# NanoV3_3_new_board.net
KiCad netlist of a schematic drawn in EAGLE
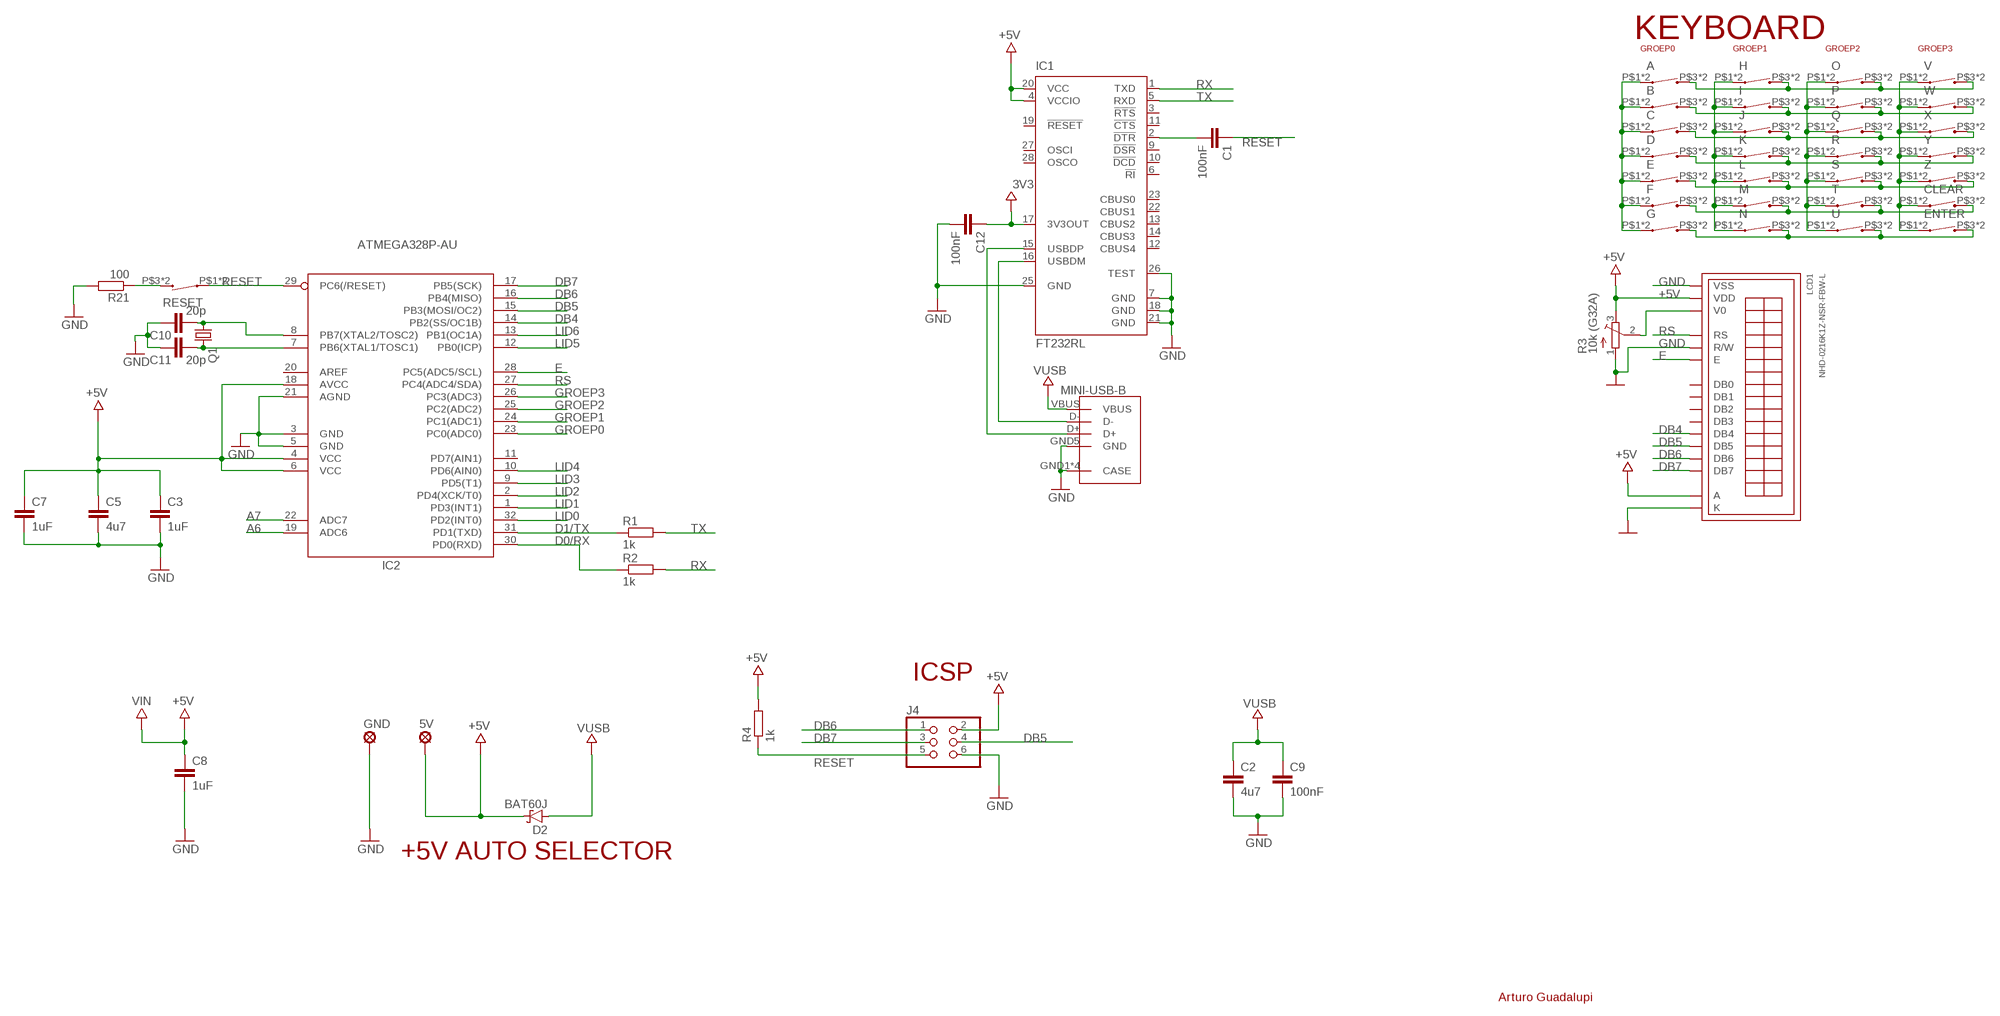
[diagram p0: schematic, sheet 1]

(export (version "E")
  (design (tool "Eeschema 10.0.6"))
  (components
    (comp (ref "5V")
      (value "LSP10")
      (footprint "eagle-import:LSP10")
      (libsource (lib "eagle-import") (part "LSP10"))
    )
    (comp (ref "A")
      (value "BRIGHTTSA061G100-250_SWITCH")
      (footprint "eagle-import:BRIGHTTSA061G100-250")
      (libsource (lib "eagle-import") (part "BRIGHTTSA061G100-250_SWITCH"))
    )
    (comp (ref "B")
      (value "BRIGHTTSA061G100-250_SWITCH")
      (footprint "eagle-import:BRIGHTTSA061G100-250")
      (libsource (lib "eagle-import") (part "BRIGHTTSA061G100-250_SWITCH"))
    )
    (comp (ref "C")
      (value "BRIGHTTSA061G100-250_SWITCH")
      (footprint "eagle-import:BRIGHTTSA061G100-250")
      (libsource (lib "eagle-import") (part "BRIGHTTSA061G100-250_SWITCH"))
    )
    (comp (ref "C1")
      (value "100nF")
      (footprint "eagle-import:C0805")
      (libsource (lib "eagle-import") (part "C-EUC0805"))
    )
    (comp (ref "C2")
      (value "4u7")
      (footprint "eagle-import:C0805")
      (libsource (lib "eagle-import") (part "C-EUC0805"))
    )
    (comp (ref "C3")
      (value "1uF")
      (footprint "eagle-import:C0805")
      (libsource (lib "eagle-import") (part "C-EUC0805"))
    )
    (comp (ref "C5")
      (value "4u7")
      (footprint "eagle-import:C0805")
      (libsource (lib "eagle-import") (part "C-EUC0805"))
    )
    (comp (ref "C7")
      (value "1uF")
      (footprint "eagle-import:C0805")
      (libsource (lib "eagle-import") (part "C-EUC0805"))
    )
    (comp (ref "C8")
      (value "1uF")
      (footprint "eagle-import:C0805")
      (libsource (lib "eagle-import") (part "C-EUC0805"))
    )
    (comp (ref "C9")
      (value "100nF")
      (footprint "eagle-import:C0805")
      (libsource (lib "eagle-import") (part "C-EUC0805"))
    )
    (comp (ref "C10")
      (value "20p")
      (footprint "eagle-import:C0805")
      (libsource (lib "eagle-import") (part "C-EUC0805"))
    )
    (comp (ref "C11")
      (value "20p")
      (footprint "eagle-import:C0805")
      (libsource (lib "eagle-import") (part "C-EUC0805"))
    )
    (comp (ref "C12")
      (value "100nF")
      (footprint "eagle-import:C0805")
      (libsource (lib "eagle-import") (part "C-EUC0805"))
    )
    (comp (ref "CLEAR")
      (value "BRIGHTTSA061G100-250_SWITCH")
      (footprint "eagle-import:BRIGHTTSA061G100-250")
      (libsource (lib "eagle-import") (part "BRIGHTTSA061G100-250_SWITCH"))
    )
    (comp (ref "D")
      (value "BRIGHTTSA061G100-250_SWITCH")
      (footprint "eagle-import:BRIGHTTSA061G100-250")
      (libsource (lib "eagle-import") (part "BRIGHTTSA061G100-250_SWITCH"))
    )
    (comp (ref "D2")
      (value "BAT60J")
      (footprint "eagle-import:SOD323_ST")
      (libsource (lib "eagle-import") (part "BAT60J"))
    )
    (comp (ref "E")
      (value "BRIGHTTSA061G100-250_SWITCH")
      (footprint "eagle-import:BRIGHTTSA061G100-250")
      (libsource (lib "eagle-import") (part "BRIGHTTSA061G100-250_SWITCH"))
    )
    (comp (ref "ENTER")
      (value "BRIGHTTSA061G100-250_SWITCH")
      (footprint "eagle-import:BRIGHTTSA061G100-250")
      (libsource (lib "eagle-import") (part "BRIGHTTSA061G100-250_SWITCH"))
    )
    (comp (ref "F")
      (value "BRIGHTTSA061G100-250_SWITCH")
      (footprint "eagle-import:BRIGHTTSA061G100-250")
      (libsource (lib "eagle-import") (part "BRIGHTTSA061G100-250_SWITCH"))
    )
    (comp (ref "G")
      (value "BRIGHTTSA061G100-250_SWITCH")
      (footprint "eagle-import:BRIGHTTSA061G100-250")
      (libsource (lib "eagle-import") (part "BRIGHTTSA061G100-250_SWITCH"))
    )
    (comp (ref "GND")
      (value "LSP10")
      (footprint "eagle-import:LSP10")
      (libsource (lib "eagle-import") (part "LSP10"))
    )
    (comp (ref "H")
      (value "BRIGHTTSA061G100-250_SWITCH")
      (footprint "eagle-import:BRIGHTTSA061G100-250")
      (libsource (lib "eagle-import") (part "BRIGHTTSA061G100-250_SWITCH"))
    )
    (comp (ref "I")
      (value "BRIGHTTSA061G100-250_SWITCH")
      (footprint "eagle-import:BRIGHTTSA061G100-250")
      (libsource (lib "eagle-import") (part "BRIGHTTSA061G100-250_SWITCH"))
    )
    (comp (ref "IC1")
      (value "FT232RL")
      (footprint "eagle-import:SSOP28")
      (libsource (lib "eagle-import") (part "FT232RL"))
    )
    (comp (ref "IC2")
      (value "ATMEGA328P-AU")
      (footprint "eagle-import:TQFP32-08")
      (fields (field (name "MANUFACTURER") "ATMEL"))
      (libsource (lib "eagle-import") (part "ATMEGA328P-32AU"))
    )
    (comp (ref "J")
      (value "BRIGHTTSA061G100-250_SWITCH")
      (footprint "eagle-import:BRIGHTTSA061G100-250")
      (libsource (lib "eagle-import") (part "BRIGHTTSA061G100-250_SWITCH"))
    )
    (comp (ref "J4")
      (value "0114_PH254-203DF118A00V")
      (footprint "eagle-import:2X03")
      (fields (field (name "PART_NUMBER") "PH254-203DF118A00V"))
      (libsource (lib "eagle-import") (part "0114_PH254-203DF118A00V"))
    )
    (comp (ref "K")
      (value "BRIGHTTSA061G100-250_SWITCH")
      (footprint "eagle-import:BRIGHTTSA061G100-250")
      (libsource (lib "eagle-import") (part "BRIGHTTSA061G100-250_SWITCH"))
    )
    (comp (ref "L")
      (value "BRIGHTTSA061G100-250_SWITCH")
      (footprint "eagle-import:BRIGHTTSA061G100-250")
      (libsource (lib "eagle-import") (part "BRIGHTTSA061G100-250_SWITCH"))
    )
    (comp (ref "LCD1")
      (value "NHD-0216K1Z-NSR-FBW-L")
      (footprint "eagle-import:LCD_NO-HEAD")
      (libsource (lib "eagle-import") (part "GEN-DISPLAY-16X2-LCD"))
    )
    (comp (ref "M")
      (value "BRIGHTTSA061G100-250_SWITCH")
      (footprint "eagle-import:BRIGHTTSA061G100-250")
      (libsource (lib "eagle-import") (part "BRIGHTTSA061G100-250_SWITCH"))
    )
    (comp (ref "MINI-USB-B")
      (value "MINI_USB_B-KRHRO-SELECU-M-M5DS-W-4")
      (footprint "eagle-import:KRHROSELECU-M-M5DS-W-4")
      (libsource (lib "eagle-import") (part "MINI_USB_B-KRHRO-SELECU-M-M5DS-W-4"))
    )
    (comp (ref "N")
      (value "BRIGHTTSA061G100-250_SWITCH")
      (footprint "eagle-import:BRIGHTTSA061G100-250")
      (libsource (lib "eagle-import") (part "BRIGHTTSA061G100-250_SWITCH"))
    )
    (comp (ref "O")
      (value "BRIGHTTSA061G100-250_SWITCH")
      (footprint "eagle-import:BRIGHTTSA061G100-250")
      (libsource (lib "eagle-import") (part "BRIGHTTSA061G100-250_SWITCH"))
    )
    (comp (ref "P")
      (value "BRIGHTTSA061G100-250_SWITCH")
      (footprint "eagle-import:BRIGHTTSA061G100-250")
      (libsource (lib "eagle-import") (part "BRIGHTTSA061G100-250_SWITCH"))
    )
    (comp (ref "Q")
      (value "BRIGHTTSA061G100-250_SWITCH")
      (footprint "eagle-import:BRIGHTTSA061G100-250")
      (libsource (lib "eagle-import") (part "BRIGHTTSA061G100-250_SWITCH"))
    )
    (comp (ref "Q1")
      (value "CRYSTALHC49U70")
      (footprint "eagle-import:HC49U70")
      (libsource (lib "eagle-import") (part "CRYSTALHC49U70"))
    )
    (comp (ref "R")
      (value "BRIGHTTSA061G100-250_SWITCH")
      (footprint "eagle-import:BRIGHTTSA061G100-250")
      (libsource (lib "eagle-import") (part "BRIGHTTSA061G100-250_SWITCH"))
    )
    (comp (ref "R1")
      (value "1k")
      (footprint "eagle-import:R0805")
      (libsource (lib "eagle-import") (part "R-EU_R0805"))
    )
    (comp (ref "R2")
      (value "1k")
      (footprint "eagle-import:R0805")
      (libsource (lib "eagle-import") (part "R-EU_R0805"))
    )
    (comp (ref "R3")
      (value "10k (G32A)")
      (footprint "eagle-import:3223W")
      (libsource (lib "eagle-import") (part "TRIM_EU-3223W"))
    )
    (comp (ref "R4")
      (value "1k")
      (footprint "eagle-import:R0805")
      (libsource (lib "eagle-import") (part "R-EU_R0805"))
    )
    (comp (ref "R21")
      (value "100")
      (footprint "eagle-import:R0805")
      (libsource (lib "eagle-import") (part "R-EU_R0805"))
    )
    (comp (ref "RESET")
      (value "BRIGHTTSA061G100-250_SWITCH")
      (footprint "eagle-import:BRIGHTTSA061G100-250")
      (libsource (lib "eagle-import") (part "BRIGHTTSA061G100-250_SWITCH"))
    )
    (comp (ref "S")
      (value "BRIGHTTSA061G100-250_SWITCH")
      (footprint "eagle-import:BRIGHTTSA061G100-250")
      (libsource (lib "eagle-import") (part "BRIGHTTSA061G100-250_SWITCH"))
    )
    (comp (ref "T")
      (value "BRIGHTTSA061G100-250_SWITCH")
      (footprint "eagle-import:BRIGHTTSA061G100-250")
      (libsource (lib "eagle-import") (part "BRIGHTTSA061G100-250_SWITCH"))
    )
    (comp (ref "U")
      (value "BRIGHTTSA061G100-250_SWITCH")
      (footprint "eagle-import:BRIGHTTSA061G100-250")
      (libsource (lib "eagle-import") (part "BRIGHTTSA061G100-250_SWITCH"))
    )
    (comp (ref "V")
      (value "BRIGHTTSA061G100-250_SWITCH")
      (footprint "eagle-import:BRIGHTTSA061G100-250")
      (libsource (lib "eagle-import") (part "BRIGHTTSA061G100-250_SWITCH"))
    )
    (comp (ref "W")
      (value "BRIGHTTSA061G100-250_SWITCH")
      (footprint "eagle-import:BRIGHTTSA061G100-250")
      (libsource (lib "eagle-import") (part "BRIGHTTSA061G100-250_SWITCH"))
    )
    (comp (ref "X")
      (value "BRIGHTTSA061G100-250_SWITCH")
      (footprint "eagle-import:BRIGHTTSA061G100-250")
      (libsource (lib "eagle-import") (part "BRIGHTTSA061G100-250_SWITCH"))
    )
    (comp (ref "Y")
      (value "BRIGHTTSA061G100-250_SWITCH")
      (footprint "eagle-import:BRIGHTTSA061G100-250")
      (libsource (lib "eagle-import") (part "BRIGHTTSA061G100-250_SWITCH"))
    )
    (comp (ref "Z")
      (value "BRIGHTTSA061G100-250_SWITCH")
      (footprint "eagle-import:BRIGHTTSA061G100-250")
      (libsource (lib "eagle-import") (part "BRIGHTTSA061G100-250_SWITCH"))
    )
  )
  (nets
    (net (code "1") (name "+5V") (class "Default")
      (node (ref "5V") (pin "MP") (pinfunction "MP_MP") (pintype "passive"))
      (node (ref "C3") (pin "1") (pinfunction "1_1") (pintype "passive"))
      (node (ref "C5") (pin "1") (pinfunction "1_1") (pintype "passive"))
      (node (ref "C7") (pin "1") (pinfunction "1_1") (pintype "passive"))
      (node (ref "C8") (pin "1") (pinfunction "1_1") (pintype "passive"))
      (node (ref "D2") (pin "C") (pinfunction "C_C") (pintype "passive"))
      (node (ref "IC1") (pin "20") (pinfunction "VCC_20") (pintype "power_in"))
      (node (ref "IC1") (pin "4") (pinfunction "VCCIO_4") (pintype "power_in"))
      (node (ref "IC2") (pin "18") (pinfunction "AVCC_18") (pintype "bidirectional"))
      (node (ref "IC2") (pin "4") (pinfunction "VCC_4") (pintype "bidirectional"))
      (node (ref "IC2") (pin "6") (pinfunction "VCC_6") (pintype "bidirectional"))
      (node (ref "J4") (pin "2") (pinfunction "2_2") (pintype "passive"))
      (node (ref "LCD1") (pin "15") (pinfunction "A_15") (pintype "bidirectional"))
      (node (ref "LCD1") (pin "2") (pinfunction "VDD_2") (pintype "bidirectional"))
      (node (ref "R3") (pin "3") (pinfunction "E_3") (pintype "passive"))
      (node (ref "R4") (pin "2") (pinfunction "2_2") (pintype "passive"))
    )
    (net (code "2") (name "/A6") (class "Default")
      (node (ref "IC2") (pin "19") (pinfunction "ADC6_19") (pintype "bidirectional"))
    )
    (net (code "3") (name "/A7") (class "Default")
      (node (ref "IC2") (pin "22") (pinfunction "ADC7_22") (pintype "bidirectional"))
    )
    (net (code "4") (name "/D0{slash}RX") (class "Default")
      (node (ref "IC2") (pin "30") (pinfunction "PD0(RXD)_30") (pintype "bidirectional"))
      (node (ref "R2") (pin "1") (pinfunction "1_1") (pintype "passive"))
    )
    (net (code "5") (name "/D1{slash}TX") (class "Default")
      (node (ref "IC2") (pin "31") (pinfunction "PD1(TXD)_31") (pintype "bidirectional"))
      (node (ref "R1") (pin "1") (pinfunction "1_1") (pintype "passive"))
    )
    (net (code "6") (name "/DB4") (class "Default")
      (node (ref "IC2") (pin "14") (pinfunction "PB2(SS/OC1B)_14") (pintype "bidirectional"))
      (node (ref "LCD1") (pin "11") (pinfunction "DB4_11") (pintype "bidirectional"))
    )
    (net (code "7") (name "/DB5") (class "Default")
      (node (ref "IC2") (pin "15") (pinfunction "PB3(MOSI/OC2)_15") (pintype "bidirectional"))
      (node (ref "J4") (pin "4") (pinfunction "4_4") (pintype "passive"))
      (node (ref "LCD1") (pin "12") (pinfunction "DB5_12") (pintype "bidirectional"))
    )
    (net (code "8") (name "/DB6") (class "Default")
      (node (ref "IC2") (pin "16") (pinfunction "PB4(MISO)_16") (pintype "bidirectional"))
      (node (ref "J4") (pin "1") (pinfunction "1_1") (pintype "passive"))
      (node (ref "LCD1") (pin "13") (pinfunction "DB6_13") (pintype "bidirectional"))
    )
    (net (code "9") (name "/DB7") (class "Default")
      (node (ref "IC2") (pin "17") (pinfunction "PB5(SCK)_17") (pintype "bidirectional"))
      (node (ref "J4") (pin "3") (pinfunction "3_3") (pintype "passive"))
      (node (ref "LCD1") (pin "14") (pinfunction "DB7_14") (pintype "bidirectional"))
    )
    (net (code "10") (name "/E") (class "Default")
      (node (ref "IC2") (pin "28") (pinfunction "PC5(ADC5/SCL)_28") (pintype "bidirectional"))
      (node (ref "LCD1") (pin "6") (pinfunction "E_6") (pintype "bidirectional"))
    )
    (net (code "11") (name "/GROEP0") (class "Default")
      (node (ref "A") (pin "P$1") (pinfunction "1_P$1") (pintype "passive"))
      (node (ref "A") (pin "P$2") (pinfunction "1_P$2") (pintype "passive"))
      (node (ref "B") (pin "P$1") (pinfunction "1_P$1") (pintype "passive"))
      (node (ref "B") (pin "P$2") (pinfunction "1_P$2") (pintype "passive"))
      (node (ref "C") (pin "P$1") (pinfunction "1_P$1") (pintype "passive"))
      (node (ref "C") (pin "P$2") (pinfunction "1_P$2") (pintype "passive"))
      (node (ref "D") (pin "P$1") (pinfunction "1_P$1") (pintype "passive"))
      (node (ref "D") (pin "P$2") (pinfunction "1_P$2") (pintype "passive"))
      (node (ref "E") (pin "P$1") (pinfunction "1_P$1") (pintype "passive"))
      (node (ref "E") (pin "P$2") (pinfunction "1_P$2") (pintype "passive"))
      (node (ref "F") (pin "P$1") (pinfunction "1_P$1") (pintype "passive"))
      (node (ref "F") (pin "P$2") (pinfunction "1_P$2") (pintype "passive"))
      (node (ref "G") (pin "P$1") (pinfunction "1_P$1") (pintype "passive"))
      (node (ref "G") (pin "P$2") (pinfunction "1_P$2") (pintype "passive"))
      (node (ref "IC2") (pin "23") (pinfunction "PC0(ADC0)_23") (pintype "bidirectional"))
    )
    (net (code "12") (name "/GROEP1") (class "Default")
      (node (ref "H") (pin "P$1") (pinfunction "1_P$1") (pintype "passive"))
      (node (ref "H") (pin "P$2") (pinfunction "1_P$2") (pintype "passive"))
      (node (ref "I") (pin "P$1") (pinfunction "1_P$1") (pintype "passive"))
      (node (ref "I") (pin "P$2") (pinfunction "1_P$2") (pintype "passive"))
      (node (ref "IC2") (pin "24") (pinfunction "PC1(ADC1)_24") (pintype "bidirectional"))
      (node (ref "J") (pin "P$1") (pinfunction "1_P$1") (pintype "passive"))
      (node (ref "J") (pin "P$2") (pinfunction "1_P$2") (pintype "passive"))
      (node (ref "K") (pin "P$1") (pinfunction "1_P$1") (pintype "passive"))
      (node (ref "K") (pin "P$2") (pinfunction "1_P$2") (pintype "passive"))
      (node (ref "L") (pin "P$1") (pinfunction "1_P$1") (pintype "passive"))
      (node (ref "L") (pin "P$2") (pinfunction "1_P$2") (pintype "passive"))
      (node (ref "M") (pin "P$1") (pinfunction "1_P$1") (pintype "passive"))
      (node (ref "M") (pin "P$2") (pinfunction "1_P$2") (pintype "passive"))
      (node (ref "N") (pin "P$1") (pinfunction "1_P$1") (pintype "passive"))
      (node (ref "N") (pin "P$2") (pinfunction "1_P$2") (pintype "passive"))
    )
    (net (code "13") (name "/GROEP2") (class "Default")
      (node (ref "IC2") (pin "25") (pinfunction "PC2(ADC2)_25") (pintype "bidirectional"))
      (node (ref "O") (pin "P$1") (pinfunction "1_P$1") (pintype "passive"))
      (node (ref "O") (pin "P$2") (pinfunction "1_P$2") (pintype "passive"))
      (node (ref "P") (pin "P$1") (pinfunction "1_P$1") (pintype "passive"))
      (node (ref "P") (pin "P$2") (pinfunction "1_P$2") (pintype "passive"))
      (node (ref "Q") (pin "P$1") (pinfunction "1_P$1") (pintype "passive"))
      (node (ref "Q") (pin "P$2") (pinfunction "1_P$2") (pintype "passive"))
      (node (ref "R") (pin "P$1") (pinfunction "1_P$1") (pintype "passive"))
      (node (ref "R") (pin "P$2") (pinfunction "1_P$2") (pintype "passive"))
      (node (ref "S") (pin "P$1") (pinfunction "1_P$1") (pintype "passive"))
      (node (ref "S") (pin "P$2") (pinfunction "1_P$2") (pintype "passive"))
      (node (ref "T") (pin "P$1") (pinfunction "1_P$1") (pintype "passive"))
      (node (ref "T") (pin "P$2") (pinfunction "1_P$2") (pintype "passive"))
      (node (ref "U") (pin "P$1") (pinfunction "1_P$1") (pintype "passive"))
      (node (ref "U") (pin "P$2") (pinfunction "1_P$2") (pintype "passive"))
    )
    (net (code "14") (name "/GROEP3") (class "Default")
      (node (ref "CLEAR") (pin "P$1") (pinfunction "1_P$1") (pintype "passive"))
      (node (ref "CLEAR") (pin "P$2") (pinfunction "1_P$2") (pintype "passive"))
      (node (ref "ENTER") (pin "P$1") (pinfunction "1_P$1") (pintype "passive"))
      (node (ref "ENTER") (pin "P$2") (pinfunction "1_P$2") (pintype "passive"))
      (node (ref "IC2") (pin "26") (pinfunction "PC3(ADC3)_26") (pintype "bidirectional"))
      (node (ref "V") (pin "P$1") (pinfunction "1_P$1") (pintype "passive"))
      (node (ref "V") (pin "P$2") (pinfunction "1_P$2") (pintype "passive"))
      (node (ref "W") (pin "P$1") (pinfunction "1_P$1") (pintype "passive"))
      (node (ref "W") (pin "P$2") (pinfunction "1_P$2") (pintype "passive"))
      (node (ref "X") (pin "P$1") (pinfunction "1_P$1") (pintype "passive"))
      (node (ref "X") (pin "P$2") (pinfunction "1_P$2") (pintype "passive"))
      (node (ref "Y") (pin "P$1") (pinfunction "1_P$1") (pintype "passive"))
      (node (ref "Y") (pin "P$2") (pinfunction "1_P$2") (pintype "passive"))
      (node (ref "Z") (pin "P$1") (pinfunction "1_P$1") (pintype "passive"))
      (node (ref "Z") (pin "P$2") (pinfunction "1_P$2") (pintype "passive"))
    )
    (net (code "15") (name "/LID0") (class "Default")
      (node (ref "A") (pin "P$3") (pinfunction "2_P$3") (pintype "passive"))
      (node (ref "A") (pin "P$4") (pinfunction "2_P$4") (pintype "passive"))
      (node (ref "H") (pin "P$3") (pinfunction "2_P$3") (pintype "passive"))
      (node (ref "H") (pin "P$4") (pinfunction "2_P$4") (pintype "passive"))
      (node (ref "IC2") (pin "32") (pinfunction "PD2(INT0)_32") (pintype "bidirectional"))
      (node (ref "O") (pin "P$3") (pinfunction "2_P$3") (pintype "passive"))
      (node (ref "O") (pin "P$4") (pinfunction "2_P$4") (pintype "passive"))
      (node (ref "V") (pin "P$3") (pinfunction "2_P$3") (pintype "passive"))
      (node (ref "V") (pin "P$4") (pinfunction "2_P$4") (pintype "passive"))
    )
    (net (code "16") (name "/LID1") (class "Default")
      (node (ref "B") (pin "P$3") (pinfunction "2_P$3") (pintype "passive"))
      (node (ref "B") (pin "P$4") (pinfunction "2_P$4") (pintype "passive"))
      (node (ref "I") (pin "P$3") (pinfunction "2_P$3") (pintype "passive"))
      (node (ref "I") (pin "P$4") (pinfunction "2_P$4") (pintype "passive"))
      (node (ref "IC2") (pin "1") (pinfunction "PD3(INT1)_1") (pintype "bidirectional"))
      (node (ref "P") (pin "P$3") (pinfunction "2_P$3") (pintype "passive"))
      (node (ref "P") (pin "P$4") (pinfunction "2_P$4") (pintype "passive"))
      (node (ref "W") (pin "P$3") (pinfunction "2_P$3") (pintype "passive"))
      (node (ref "W") (pin "P$4") (pinfunction "2_P$4") (pintype "passive"))
    )
    (net (code "17") (name "/LID2") (class "Default")
      (node (ref "C") (pin "P$3") (pinfunction "2_P$3") (pintype "passive"))
      (node (ref "C") (pin "P$4") (pinfunction "2_P$4") (pintype "passive"))
      (node (ref "IC2") (pin "2") (pinfunction "PD4(XCK/T0)_2") (pintype "bidirectional"))
      (node (ref "J") (pin "P$3") (pinfunction "2_P$3") (pintype "passive"))
      (node (ref "J") (pin "P$4") (pinfunction "2_P$4") (pintype "passive"))
      (node (ref "Q") (pin "P$3") (pinfunction "2_P$3") (pintype "passive"))
      (node (ref "Q") (pin "P$4") (pinfunction "2_P$4") (pintype "passive"))
      (node (ref "X") (pin "P$3") (pinfunction "2_P$3") (pintype "passive"))
      (node (ref "X") (pin "P$4") (pinfunction "2_P$4") (pintype "passive"))
    )
    (net (code "18") (name "/LID3") (class "Default")
      (node (ref "D") (pin "P$3") (pinfunction "2_P$3") (pintype "passive"))
      (node (ref "D") (pin "P$4") (pinfunction "2_P$4") (pintype "passive"))
      (node (ref "IC2") (pin "9") (pinfunction "PD5(T1)_9") (pintype "bidirectional"))
      (node (ref "K") (pin "P$3") (pinfunction "2_P$3") (pintype "passive"))
      (node (ref "K") (pin "P$4") (pinfunction "2_P$4") (pintype "passive"))
      (node (ref "R") (pin "P$3") (pinfunction "2_P$3") (pintype "passive"))
      (node (ref "R") (pin "P$4") (pinfunction "2_P$4") (pintype "passive"))
      (node (ref "Y") (pin "P$3") (pinfunction "2_P$3") (pintype "passive"))
      (node (ref "Y") (pin "P$4") (pinfunction "2_P$4") (pintype "passive"))
    )
    (net (code "19") (name "/LID4") (class "Default")
      (node (ref "E") (pin "P$3") (pinfunction "2_P$3") (pintype "passive"))
      (node (ref "E") (pin "P$4") (pinfunction "2_P$4") (pintype "passive"))
      (node (ref "IC2") (pin "10") (pinfunction "PD6(AIN0)_10") (pintype "bidirectional"))
      (node (ref "L") (pin "P$3") (pinfunction "2_P$3") (pintype "passive"))
      (node (ref "L") (pin "P$4") (pinfunction "2_P$4") (pintype "passive"))
      (node (ref "S") (pin "P$3") (pinfunction "2_P$3") (pintype "passive"))
      (node (ref "S") (pin "P$4") (pinfunction "2_P$4") (pintype "passive"))
      (node (ref "Z") (pin "P$3") (pinfunction "2_P$3") (pintype "passive"))
      (node (ref "Z") (pin "P$4") (pinfunction "2_P$4") (pintype "passive"))
    )
    (net (code "20") (name "/LID5") (class "Default")
      (node (ref "CLEAR") (pin "P$3") (pinfunction "2_P$3") (pintype "passive"))
      (node (ref "CLEAR") (pin "P$4") (pinfunction "2_P$4") (pintype "passive"))
      (node (ref "F") (pin "P$3") (pinfunction "2_P$3") (pintype "passive"))
      (node (ref "F") (pin "P$4") (pinfunction "2_P$4") (pintype "passive"))
      (node (ref "IC2") (pin "12") (pinfunction "PB0(ICP)_12") (pintype "bidirectional"))
      (node (ref "M") (pin "P$3") (pinfunction "2_P$3") (pintype "passive"))
      (node (ref "M") (pin "P$4") (pinfunction "2_P$4") (pintype "passive"))
      (node (ref "T") (pin "P$3") (pinfunction "2_P$3") (pintype "passive"))
      (node (ref "T") (pin "P$4") (pinfunction "2_P$4") (pintype "passive"))
    )
    (net (code "21") (name "/LID6") (class "Default")
      (node (ref "ENTER") (pin "P$3") (pinfunction "2_P$3") (pintype "passive"))
      (node (ref "ENTER") (pin "P$4") (pinfunction "2_P$4") (pintype "passive"))
      (node (ref "G") (pin "P$3") (pinfunction "2_P$3") (pintype "passive"))
      (node (ref "G") (pin "P$4") (pinfunction "2_P$4") (pintype "passive"))
      (node (ref "IC2") (pin "13") (pinfunction "PB1(OC1A)_13") (pintype "bidirectional"))
      (node (ref "N") (pin "P$3") (pinfunction "2_P$3") (pintype "passive"))
      (node (ref "N") (pin "P$4") (pinfunction "2_P$4") (pintype "passive"))
      (node (ref "U") (pin "P$3") (pinfunction "2_P$3") (pintype "passive"))
      (node (ref "U") (pin "P$4") (pinfunction "2_P$4") (pintype "passive"))
    )
    (net (code "22") (name "/RESET") (class "Default")
      (node (ref "C1") (pin "1") (pinfunction "1_1") (pintype "passive"))
      (node (ref "IC2") (pin "29") (pinfunction "PC6(/RESET)_29") (pintype "bidirectional"))
      (node (ref "J4") (pin "5") (pinfunction "5_5") (pintype "passive"))
      (node (ref "R4") (pin "1") (pinfunction "1_1") (pintype "passive"))
      (node (ref "RESET") (pin "P$1") (pinfunction "1_P$1") (pintype "passive"))
      (node (ref "RESET") (pin "P$2") (pinfunction "1_P$2") (pintype "passive"))
    )
    (net (code "23") (name "/RS") (class "Default")
      (node (ref "IC2") (pin "27") (pinfunction "PC4(ADC4/SDA)_27") (pintype "bidirectional"))
      (node (ref "LCD1") (pin "4") (pinfunction "RS_4") (pintype "bidirectional"))
    )
    (net (code "24") (name "/RX") (class "Default")
      (node (ref "IC1") (pin "1") (pinfunction "TXD_1") (pintype "output"))
      (node (ref "R2") (pin "2") (pinfunction "2_2") (pintype "passive"))
    )
    (net (code "25") (name "/TX") (class "Default")
      (node (ref "IC1") (pin "5") (pinfunction "RXD_5") (pintype "input"))
      (node (ref "R1") (pin "2") (pinfunction "2_2") (pintype "passive"))
    )
    (net (code "26") (name "3V3") (class "Default")
      (node (ref "C12") (pin "1") (pinfunction "1_1") (pintype "passive"))
      (node (ref "IC1") (pin "17") (pinfunction "3V3OUT_17") (pintype "output"))
    )
    (net (code "27") (name "GND") (class "Default")
      (node (ref "C10") (pin "1") (pinfunction "1_1") (pintype "passive"))
      (node (ref "C11") (pin "1") (pinfunction "1_1") (pintype "passive"))
      (node (ref "C12") (pin "2") (pinfunction "2_2") (pintype "passive"))
      (node (ref "C2") (pin "2") (pinfunction "2_2") (pintype "passive"))
      (node (ref "C3") (pin "2") (pinfunction "2_2") (pintype "passive"))
      (node (ref "C5") (pin "2") (pinfunction "2_2") (pintype "passive"))
      (node (ref "C7") (pin "2") (pinfunction "2_2") (pintype "passive"))
      (node (ref "C8") (pin "2") (pinfunction "2_2") (pintype "passive"))
      (node (ref "C9") (pin "2") (pinfunction "2_2") (pintype "passive"))
      (node (ref "GND") (pin "MP") (pinfunction "MP_MP") (pintype "passive"))
      (node (ref "IC1") (pin "18") (pinfunction "GND_18") (pintype "power_in"))
      (node (ref "IC1") (pin "21") (pinfunction "GND_21") (pintype "power_in"))
      (node (ref "IC1") (pin "25") (pinfunction "GND_25") (pintype "power_in"))
      (node (ref "IC1") (pin "26") (pinfunction "TEST_26") (pintype "input"))
      (node (ref "IC1") (pin "7") (pinfunction "GND_7") (pintype "power_in"))
      (node (ref "IC2") (pin "21") (pinfunction "AGND_21") (pintype "bidirectional"))
      (node (ref "IC2") (pin "3") (pinfunction "GND_3") (pintype "bidirectional"))
      (node (ref "IC2") (pin "5") (pinfunction "GND_5") (pintype "bidirectional"))
      (node (ref "J4") (pin "6") (pinfunction "6_6") (pintype "passive"))
      (node (ref "LCD1") (pin "1") (pinfunction "VSS_1") (pintype "bidirectional"))
      (node (ref "LCD1") (pin "16") (pinfunction "K_16") (pintype "bidirectional"))
      (node (ref "LCD1") (pin "5") (pinfunction "R/W_5") (pintype "bidirectional"))
      (node (ref "MINI-USB-B") (pin "GND1") (pinfunction "CASE_GND1") (pintype "bidirectional"))
      (node (ref "MINI-USB-B") (pin "GND2") (pinfunction "CASE_GND2") (pintype "bidirectional"))
      (node (ref "MINI-USB-B") (pin "GND3") (pinfunction "CASE_GND3") (pintype "bidirectional"))
      (node (ref "MINI-USB-B") (pin "GND4") (pinfunction "CASE_GND4") (pintype "bidirectional"))
      (node (ref "MINI-USB-B") (pin "GND5") (pinfunction "GND_GND5") (pintype "bidirectional"))
      (node (ref "R21") (pin "2") (pinfunction "2_2") (pintype "passive"))
      (node (ref "R3") (pin "1") (pinfunction "A_1") (pintype "passive"))
    )
    (net (code "28") (name "Net-(IC1-USBDM)") (class "Default")
      (node (ref "IC1") (pin "16") (pinfunction "USBDM_16") (pintype "bidirectional"))
      (node (ref "MINI-USB-B") (pin "D-") (pinfunction "D-_D-") (pintype "bidirectional"))
    )
    (net (code "29") (name "Net-(IC1-USBDP)") (class "Default")
      (node (ref "IC1") (pin "15") (pinfunction "USBDP_15") (pintype "bidirectional"))
      (node (ref "MINI-USB-B") (pin "D+") (pinfunction "D+_D+") (pintype "bidirectional"))
    )
    (net (code "30") (name "Net-(IC1-~{DTR})") (class "Default")
      (node (ref "C1") (pin "2") (pinfunction "2_2") (pintype "passive"))
      (node (ref "IC1") (pin "2") (pinfunction "~{DTR}_2") (pintype "output"))
    )
    (net (code "31") (name "Net-(IC2-PB6(XTAL1{slash}TOSC1))") (class "Default")
      (node (ref "C11") (pin "2") (pinfunction "2_2") (pintype "passive"))
      (node (ref "IC2") (pin "7") (pinfunction "PB6(XTAL1/TOSC1)_7") (pintype "bidirectional"))
      (node (ref "Q1") (pin "2") (pinfunction "2_2") (pintype "passive"))
    )
    (net (code "32") (name "Net-(IC2-PB7(XTAL2{slash}TOSC2))") (class "Default")
      (node (ref "C10") (pin "2") (pinfunction "2_2") (pintype "passive"))
      (node (ref "IC2") (pin "8") (pinfunction "PB7(XTAL2/TOSC2)_8") (pintype "bidirectional"))
      (node (ref "Q1") (pin "1") (pinfunction "1_1") (pintype "passive"))
    )
    (net (code "33") (name "Net-(LCD1-V0)") (class "Default")
      (node (ref "LCD1") (pin "3") (pinfunction "V0_3") (pintype "bidirectional"))
      (node (ref "R3") (pin "2") (pinfunction "S_2") (pintype "passive"))
    )
    (net (code "34") (name "Net-(R21-Pad1)") (class "Default")
      (node (ref "R21") (pin "1") (pinfunction "1_1") (pintype "passive"))
      (node (ref "RESET") (pin "P$3") (pinfunction "2_P$3") (pintype "passive"))
      (node (ref "RESET") (pin "P$4") (pinfunction "2_P$4") (pintype "passive"))
    )
    (net (code "35") (name "VUSB") (class "Default")
      (node (ref "C2") (pin "1") (pinfunction "1_1") (pintype "passive"))
      (node (ref "C9") (pin "1") (pinfunction "1_1") (pintype "passive"))
      (node (ref "D2") (pin "A") (pinfunction "A_A") (pintype "passive"))
      (node (ref "MINI-USB-B") (pin "VBUS") (pinfunction "VBUS_VBUS") (pintype "bidirectional"))
    )
    (net (code "36") (name "unconnected-(IC1-CBUS0-Pad23)") (class "Default")
      (node (ref "IC1") (pin "23") (pinfunction "CBUS0_23") (pintype "bidirectional"))
    )
    (net (code "37") (name "unconnected-(IC1-CBUS1-Pad22)") (class "Default")
      (node (ref "IC1") (pin "22") (pinfunction "CBUS1_22") (pintype "bidirectional"))
    )
    (net (code "38") (name "unconnected-(IC1-CBUS2-Pad13)") (class "Default")
      (node (ref "IC1") (pin "13") (pinfunction "CBUS2_13") (pintype "bidirectional"))
    )
    (net (code "39") (name "unconnected-(IC1-CBUS3-Pad14)") (class "Default")
      (node (ref "IC1") (pin "14") (pinfunction "CBUS3_14") (pintype "bidirectional"))
    )
    (net (code "40") (name "unconnected-(IC1-CBUS4-Pad12)") (class "Default")
      (node (ref "IC1") (pin "12") (pinfunction "CBUS4_12") (pintype "bidirectional"))
    )
    (net (code "41") (name "unconnected-(IC1-OSCI-Pad27)") (class "Default")
      (node (ref "IC1") (pin "27") (pinfunction "OSCI_27") (pintype "input"))
    )
    (net (code "42") (name "unconnected-(IC1-OSCO-Pad28)") (class "Default")
      (node (ref "IC1") (pin "28") (pinfunction "OSCO_28") (pintype "output"))
    )
    (net (code "43") (name "unconnected-(IC1-~{CTS}-Pad11)") (class "Default")
      (node (ref "IC1") (pin "11") (pinfunction "~{CTS}_11") (pintype "input"))
    )
    (net (code "44") (name "unconnected-(IC1-~{DCD}-Pad10)") (class "Default")
      (node (ref "IC1") (pin "10") (pinfunction "~{DCD}_10") (pintype "input"))
    )
    (net (code "45") (name "unconnected-(IC1-~{DSR}-Pad9)") (class "Default")
      (node (ref "IC1") (pin "9") (pinfunction "~{DSR}_9") (pintype "input"))
    )
    (net (code "46") (name "unconnected-(IC1-~{RESET}-Pad19)") (class "Default")
      (node (ref "IC1") (pin "19") (pinfunction "~{RESET}_19") (pintype "input"))
    )
    (net (code "47") (name "unconnected-(IC1-~{RI}-Pad6)") (class "Default")
      (node (ref "IC1") (pin "6") (pinfunction "~{RI}_6") (pintype "input"))
    )
    (net (code "48") (name "unconnected-(IC1-~{RTS}-Pad3)") (class "Default")
      (node (ref "IC1") (pin "3") (pinfunction "~{RTS}_3") (pintype "output"))
    )
    (net (code "49") (name "unconnected-(IC2-AREF-Pad20)") (class "Default")
      (node (ref "IC2") (pin "20") (pinfunction "AREF_20") (pintype "bidirectional"))
    )
    (net (code "50") (name "unconnected-(IC2-PD7(AIN1)-Pad11)") (class "Default")
      (node (ref "IC2") (pin "11") (pinfunction "PD7(AIN1)_11") (pintype "bidirectional"))
    )
    (net (code "51") (name "unconnected-(LCD1-DB0-Pad7)") (class "Default")
      (node (ref "LCD1") (pin "7") (pinfunction "DB0_7") (pintype "bidirectional"))
    )
    (net (code "52") (name "unconnected-(LCD1-DB1-Pad8)") (class "Default")
      (node (ref "LCD1") (pin "8") (pinfunction "DB1_8") (pintype "bidirectional"))
    )
    (net (code "53") (name "unconnected-(LCD1-DB2-Pad9)") (class "Default")
      (node (ref "LCD1") (pin "9") (pinfunction "DB2_9") (pintype "bidirectional"))
    )
    (net (code "54") (name "unconnected-(LCD1-DB3-Pad10)") (class "Default")
      (node (ref "LCD1") (pin "10") (pinfunction "DB3_10") (pintype "bidirectional"))
    )
  )
)
